# pcb.net
KiCad netlist of a schematic drawn in EAGLE
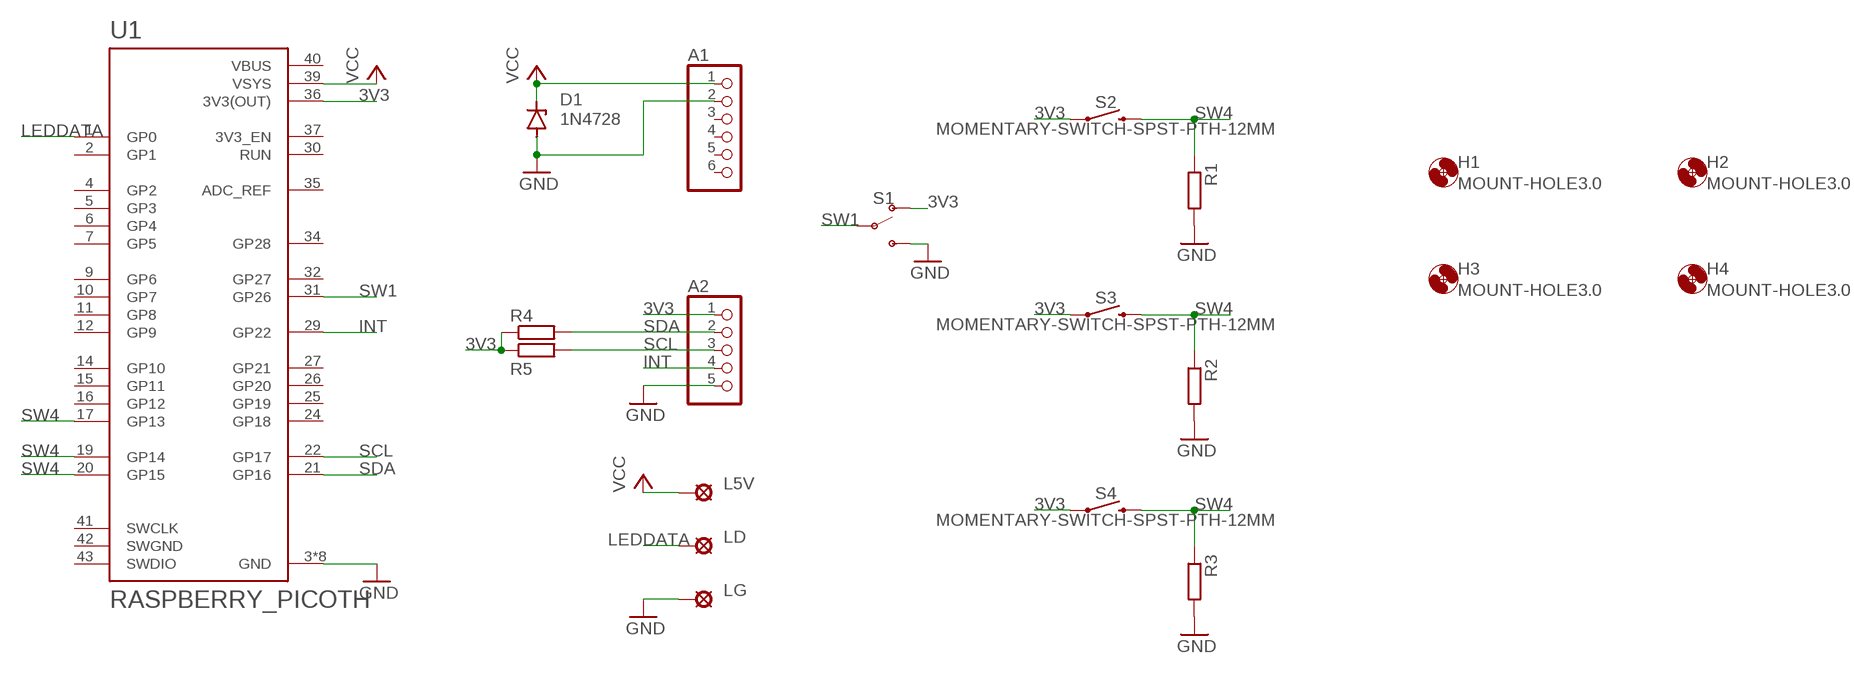
[diagram p0: schematic, sheet 1]

(export (version "E")
  (design (tool "Eeschema 10.0.6"))
  (components
    (comp (ref "A1")
      (value "PINHD-1X6")
      (footprint "eagle-import:1X06")
      (libsource (lib "eagle-import") (part "PINHD-1X6"))
    )
    (comp (ref "A2")
      (value "PINHD-1X5")
      (footprint "eagle-import:1X05")
      (libsource (lib "eagle-import") (part "PINHD-1X5"))
    )
    (comp (ref "D1")
      (value "1N4728")
      (footprint "eagle-import:DO41Z10")
      (libsource (lib "eagle-import") (part "1N4728"))
    )
    (comp (ref "H1")
      (value "MOUNT-HOLE3.0")
      (footprint "eagle-import:3,0")
      (libsource (lib "eagle-import") (part "MOUNT-HOLE3.0"))
    )
    (comp (ref "H2")
      (value "MOUNT-HOLE3.0")
      (footprint "eagle-import:3,0")
      (libsource (lib "eagle-import") (part "MOUNT-HOLE3.0"))
    )
    (comp (ref "H3")
      (value "MOUNT-HOLE3.0")
      (footprint "eagle-import:3,0")
      (libsource (lib "eagle-import") (part "MOUNT-HOLE3.0"))
    )
    (comp (ref "H4")
      (value "MOUNT-HOLE3.0")
      (footprint "eagle-import:3,0")
      (libsource (lib "eagle-import") (part "MOUNT-HOLE3.0"))
    )
    (comp (ref "L5V")
      (value "LSP10")
      (footprint "eagle-import:LSP10")
      (libsource (lib "eagle-import") (part "LSP10"))
    )
    (comp (ref "LD")
      (value "LSP10")
      (footprint "eagle-import:LSP10")
      (libsource (lib "eagle-import") (part "LSP10"))
    )
    (comp (ref "LG")
      (value "LSP10")
      (footprint "eagle-import:LSP10")
      (libsource (lib "eagle-import") (part "LSP10"))
    )
    (comp (ref "R1")
      (value "R-EU_0207/7")
      (footprint "eagle-import:0207_7")
      (libsource (lib "eagle-import") (part "R-EU_0207/7"))
    )
    (comp (ref "R2")
      (value "R-EU_0207/7")
      (footprint "eagle-import:0207_7")
      (libsource (lib "eagle-import") (part "R-EU_0207/7"))
    )
    (comp (ref "R3")
      (value "R-EU_0207/7")
      (footprint "eagle-import:0207_7")
      (libsource (lib "eagle-import") (part "R-EU_0207/7"))
    )
    (comp (ref "R4")
      (value "R-EU_0207/7")
      (footprint "eagle-import:0207_7")
      (libsource (lib "eagle-import") (part "R-EU_0207/7"))
    )
    (comp (ref "R5")
      (value "R-EU_0207/7")
      (footprint "eagle-import:0207_7")
      (libsource (lib "eagle-import") (part "R-EU_0207/7"))
    )
    (comp (ref "S1")
      (value "SWITCH-SPDT-PTH-11.6X4.0MM-LOCK")
      (footprint "eagle-import:SWITCH_SPDT_PTH_11.6X4.0MM_LOCK")
      (libsource (lib "eagle-import") (part "SWITCH-SPDT-PTH-11.6X4.0MM-LOCK"))
    )
    (comp (ref "S2")
      (value "MOMENTARY-SWITCH-SPST-PTH-12MM")
      (footprint "eagle-import:TACTILE_SWITCH_PTH_12MM")
      (libsource (lib "eagle-import") (part "MOMENTARY-SWITCH-SPST-PTH-12MM"))
    )
    (comp (ref "S3")
      (value "MOMENTARY-SWITCH-SPST-PTH-12MM")
      (footprint "eagle-import:TACTILE_SWITCH_PTH_12MM")
      (libsource (lib "eagle-import") (part "MOMENTARY-SWITCH-SPST-PTH-12MM"))
    )
    (comp (ref "S4")
      (value "MOMENTARY-SWITCH-SPST-PTH-12MM")
      (footprint "eagle-import:TACTILE_SWITCH_PTH_12MM")
      (libsource (lib "eagle-import") (part "MOMENTARY-SWITCH-SPST-PTH-12MM"))
    )
    (comp (ref "U1")
      (value "RASPBERRY_PICOTH")
      (footprint "eagle-import:PICO-PKG-TH")
      (libsource (lib "eagle-import") (part "RASPBERRY_PICOTH"))
    )
  )
  (nets
    (net (code "1") (name "/3V3") (class "Default")
      (node (ref "A2") (pin "1") (pinfunction "1_1") (pintype "passive"))
      (node (ref "R4") (pin "1") (pinfunction "1_1") (pintype "passive"))
      (node (ref "R5") (pin "1") (pinfunction "1_1") (pintype "passive"))
      (node (ref "S1") (pin "1") (pinfunction "O_1") (pintype "passive"))
      (node (ref "S2") (pin "1") (pinfunction "1_1") (pintype "passive"))
      (node (ref "S3") (pin "1") (pinfunction "1_1") (pintype "passive"))
      (node (ref "S4") (pin "1") (pinfunction "1_1") (pintype "passive"))
      (node (ref "U1") (pin "36") (pinfunction "3V3(OUT)_36") (pintype "power_in"))
    )
    (net (code "2") (name "/INT") (class "Default")
      (node (ref "A2") (pin "4") (pinfunction "4_4") (pintype "passive"))
      (node (ref "U1") (pin "29") (pinfunction "GP22_29") (pintype "bidirectional"))
    )
    (net (code "3") (name "/LEDDATA") (class "Default")
      (node (ref "LD") (pin "MP") (pinfunction "MP_MP") (pintype "passive"))
      (node (ref "U1") (pin "1") (pinfunction "GP0_1") (pintype "bidirectional"))
    )
    (net (code "4") (name "/SCL") (class "Default")
      (node (ref "A2") (pin "3") (pinfunction "3_3") (pintype "passive"))
      (node (ref "R5") (pin "2") (pinfunction "2_2") (pintype "passive"))
      (node (ref "U1") (pin "22") (pinfunction "GP17_22") (pintype "bidirectional"))
    )
    (net (code "5") (name "/SDA") (class "Default")
      (node (ref "A2") (pin "2") (pinfunction "2_2") (pintype "passive"))
      (node (ref "R4") (pin "2") (pinfunction "2_2") (pintype "passive"))
      (node (ref "U1") (pin "21") (pinfunction "GP16_21") (pintype "bidirectional"))
    )
    (net (code "6") (name "/SW1") (class "Default")
      (node (ref "S1") (pin "2") (pinfunction "P_2") (pintype "passive"))
      (node (ref "U1") (pin "31") (pinfunction "GP26_31") (pintype "bidirectional"))
    )
    (net (code "7") (name "/SW4") (class "Default")
      (node (ref "R1") (pin "1") (pinfunction "1_1") (pintype "passive"))
      (node (ref "R2") (pin "1") (pinfunction "1_1") (pintype "passive"))
      (node (ref "R3") (pin "1") (pinfunction "1_1") (pintype "passive"))
      (node (ref "S2") (pin "3") (pinfunction "2_3") (pintype "passive"))
      (node (ref "S3") (pin "3") (pinfunction "2_3") (pintype "passive"))
      (node (ref "S4") (pin "3") (pinfunction "2_3") (pintype "passive"))
      (node (ref "U1") (pin "17") (pinfunction "GP13_17") (pintype "bidirectional"))
      (node (ref "U1") (pin "19") (pinfunction "GP14_19") (pintype "bidirectional"))
      (node (ref "U1") (pin "20") (pinfunction "GP15_20") (pintype "bidirectional"))
    )
    (net (code "8") (name "/SWGND") (class "Default")
      (node (ref "U1") (pin "42") (pinfunction "SWGND_42") (pintype "power_in"))
    )
    (net (code "9") (name "/VBUS") (class "Default")
      (node (ref "U1") (pin "40") (pinfunction "VBUS_40") (pintype "power_in"))
    )
    (net (code "10") (name "GND") (class "Default")
      (node (ref "A1") (pin "2") (pinfunction "2_2") (pintype "passive"))
      (node (ref "A2") (pin "5") (pinfunction "5_5") (pintype "passive"))
      (node (ref "D1") (pin "A") (pinfunction "A_A") (pintype "passive"))
      (node (ref "LG") (pin "MP") (pinfunction "MP_MP") (pintype "passive"))
      (node (ref "R1") (pin "2") (pinfunction "2_2") (pintype "passive"))
      (node (ref "R2") (pin "2") (pinfunction "2_2") (pintype "passive"))
      (node (ref "R3") (pin "2") (pinfunction "2_2") (pintype "passive"))
      (node (ref "S1") (pin "3") (pinfunction "S_3") (pintype "passive"))
      (node (ref "U1") (pin "13") (pinfunction "GND_13") (pintype "power_in"))
      (node (ref "U1") (pin "18") (pinfunction "GND_18") (pintype "power_in"))
      (node (ref "U1") (pin "23") (pinfunction "GND_23") (pintype "power_in"))
      (node (ref "U1") (pin "28") (pinfunction "GND_28") (pintype "power_in"))
      (node (ref "U1") (pin "3") (pinfunction "GND_3") (pintype "power_in"))
      (node (ref "U1") (pin "33") (pinfunction "GND_33") (pintype "power_in"))
      (node (ref "U1") (pin "38") (pinfunction "GND_38") (pintype "power_in"))
      (node (ref "U1") (pin "8") (pinfunction "GND_8") (pintype "power_in"))
    )
    (net (code "11") (name "VCC") (class "Default")
      (node (ref "A1") (pin "1") (pinfunction "1_1") (pintype "passive"))
      (node (ref "D1") (pin "C") (pinfunction "C_C") (pintype "passive"))
      (node (ref "L5V") (pin "MP") (pinfunction "MP_MP") (pintype "passive"))
      (node (ref "U1") (pin "39") (pinfunction "VSYS_39") (pintype "power_in"))
    )
    (net (code "12") (name "unconnected-(A1-Pad3)") (class "Default")
      (node (ref "A1") (pin "3") (pinfunction "3_3") (pintype "passive"))
    )
    (net (code "13") (name "unconnected-(A1-Pad4)") (class "Default")
      (node (ref "A1") (pin "4") (pinfunction "4_4") (pintype "passive"))
    )
    (net (code "14") (name "unconnected-(A1-Pad5)") (class "Default")
      (node (ref "A1") (pin "5") (pinfunction "5_5") (pintype "passive"))
    )
    (net (code "15") (name "unconnected-(A1-Pad6)") (class "Default")
      (node (ref "A1") (pin "6") (pinfunction "6_6") (pintype "passive"))
    )
    (net (code "16") (name "unconnected-(U1-3V3_EN-Pad37)") (class "Default")
      (node (ref "U1") (pin "37") (pinfunction "3V3_EN_37") (pintype "input"))
    )
    (net (code "17") (name "unconnected-(U1-ADC_REF-Pad35)") (class "Default")
      (node (ref "U1") (pin "35") (pinfunction "ADC_REF_35") (pintype "input"))
    )
    (net (code "18") (name "unconnected-(U1-GP1-Pad2)") (class "Default")
      (node (ref "U1") (pin "2") (pinfunction "GP1_2") (pintype "bidirectional"))
    )
    (net (code "19") (name "unconnected-(U1-GP2-Pad4)") (class "Default")
      (node (ref "U1") (pin "4") (pinfunction "GP2_4") (pintype "bidirectional"))
    )
    (net (code "20") (name "unconnected-(U1-GP3-Pad5)") (class "Default")
      (node (ref "U1") (pin "5") (pinfunction "GP3_5") (pintype "bidirectional"))
    )
    (net (code "21") (name "unconnected-(U1-GP4-Pad6)") (class "Default")
      (node (ref "U1") (pin "6") (pinfunction "GP4_6") (pintype "bidirectional"))
    )
    (net (code "22") (name "unconnected-(U1-GP5-Pad7)") (class "Default")
      (node (ref "U1") (pin "7") (pinfunction "GP5_7") (pintype "bidirectional"))
    )
    (net (code "23") (name "unconnected-(U1-GP6-Pad9)") (class "Default")
      (node (ref "U1") (pin "9") (pinfunction "GP6_9") (pintype "bidirectional"))
    )
    (net (code "24") (name "unconnected-(U1-GP7-Pad10)") (class "Default")
      (node (ref "U1") (pin "10") (pinfunction "GP7_10") (pintype "bidirectional"))
    )
    (net (code "25") (name "unconnected-(U1-GP8-Pad11)") (class "Default")
      (node (ref "U1") (pin "11") (pinfunction "GP8_11") (pintype "bidirectional"))
    )
    (net (code "26") (name "unconnected-(U1-GP9-Pad12)") (class "Default")
      (node (ref "U1") (pin "12") (pinfunction "GP9_12") (pintype "bidirectional"))
    )
    (net (code "27") (name "unconnected-(U1-GP10-Pad14)") (class "Default")
      (node (ref "U1") (pin "14") (pinfunction "GP10_14") (pintype "bidirectional"))
    )
    (net (code "28") (name "unconnected-(U1-GP11-Pad15)") (class "Default")
      (node (ref "U1") (pin "15") (pinfunction "GP11_15") (pintype "bidirectional"))
    )
    (net (code "29") (name "unconnected-(U1-GP12-Pad16)") (class "Default")
      (node (ref "U1") (pin "16") (pinfunction "GP12_16") (pintype "bidirectional"))
    )
    (net (code "30") (name "unconnected-(U1-GP18-Pad24)") (class "Default")
      (node (ref "U1") (pin "24") (pinfunction "GP18_24") (pintype "bidirectional"))
    )
    (net (code "31") (name "unconnected-(U1-GP19-Pad25)") (class "Default")
      (node (ref "U1") (pin "25") (pinfunction "GP19_25") (pintype "bidirectional"))
    )
    (net (code "32") (name "unconnected-(U1-GP20-Pad26)") (class "Default")
      (node (ref "U1") (pin "26") (pinfunction "GP20_26") (pintype "bidirectional"))
    )
    (net (code "33") (name "unconnected-(U1-GP21-Pad27)") (class "Default")
      (node (ref "U1") (pin "27") (pinfunction "GP21_27") (pintype "bidirectional"))
    )
    (net (code "34") (name "unconnected-(U1-GP27-Pad32)") (class "Default")
      (node (ref "U1") (pin "32") (pinfunction "GP27_32") (pintype "bidirectional"))
    )
    (net (code "35") (name "unconnected-(U1-GP28-Pad34)") (class "Default")
      (node (ref "U1") (pin "34") (pinfunction "GP28_34") (pintype "bidirectional"))
    )
    (net (code "36") (name "unconnected-(U1-RUN-Pad30)") (class "Default")
      (node (ref "U1") (pin "30") (pinfunction "RUN_30") (pintype "input"))
    )
    (net (code "37") (name "unconnected-(U1-SWCLK-Pad41)") (class "Default")
      (node (ref "U1") (pin "41") (pinfunction "SWCLK_41") (pintype "input"))
    )
    (net (code "38") (name "unconnected-(U1-SWDIO-Pad43)") (class "Default")
      (node (ref "U1") (pin "43") (pinfunction "SWDIO_43") (pintype "bidirectional"))
    )
  )
)
